# EJECTION_CIRCUIT.net
KiCad netlist of a schematic drawn in Altium Designer
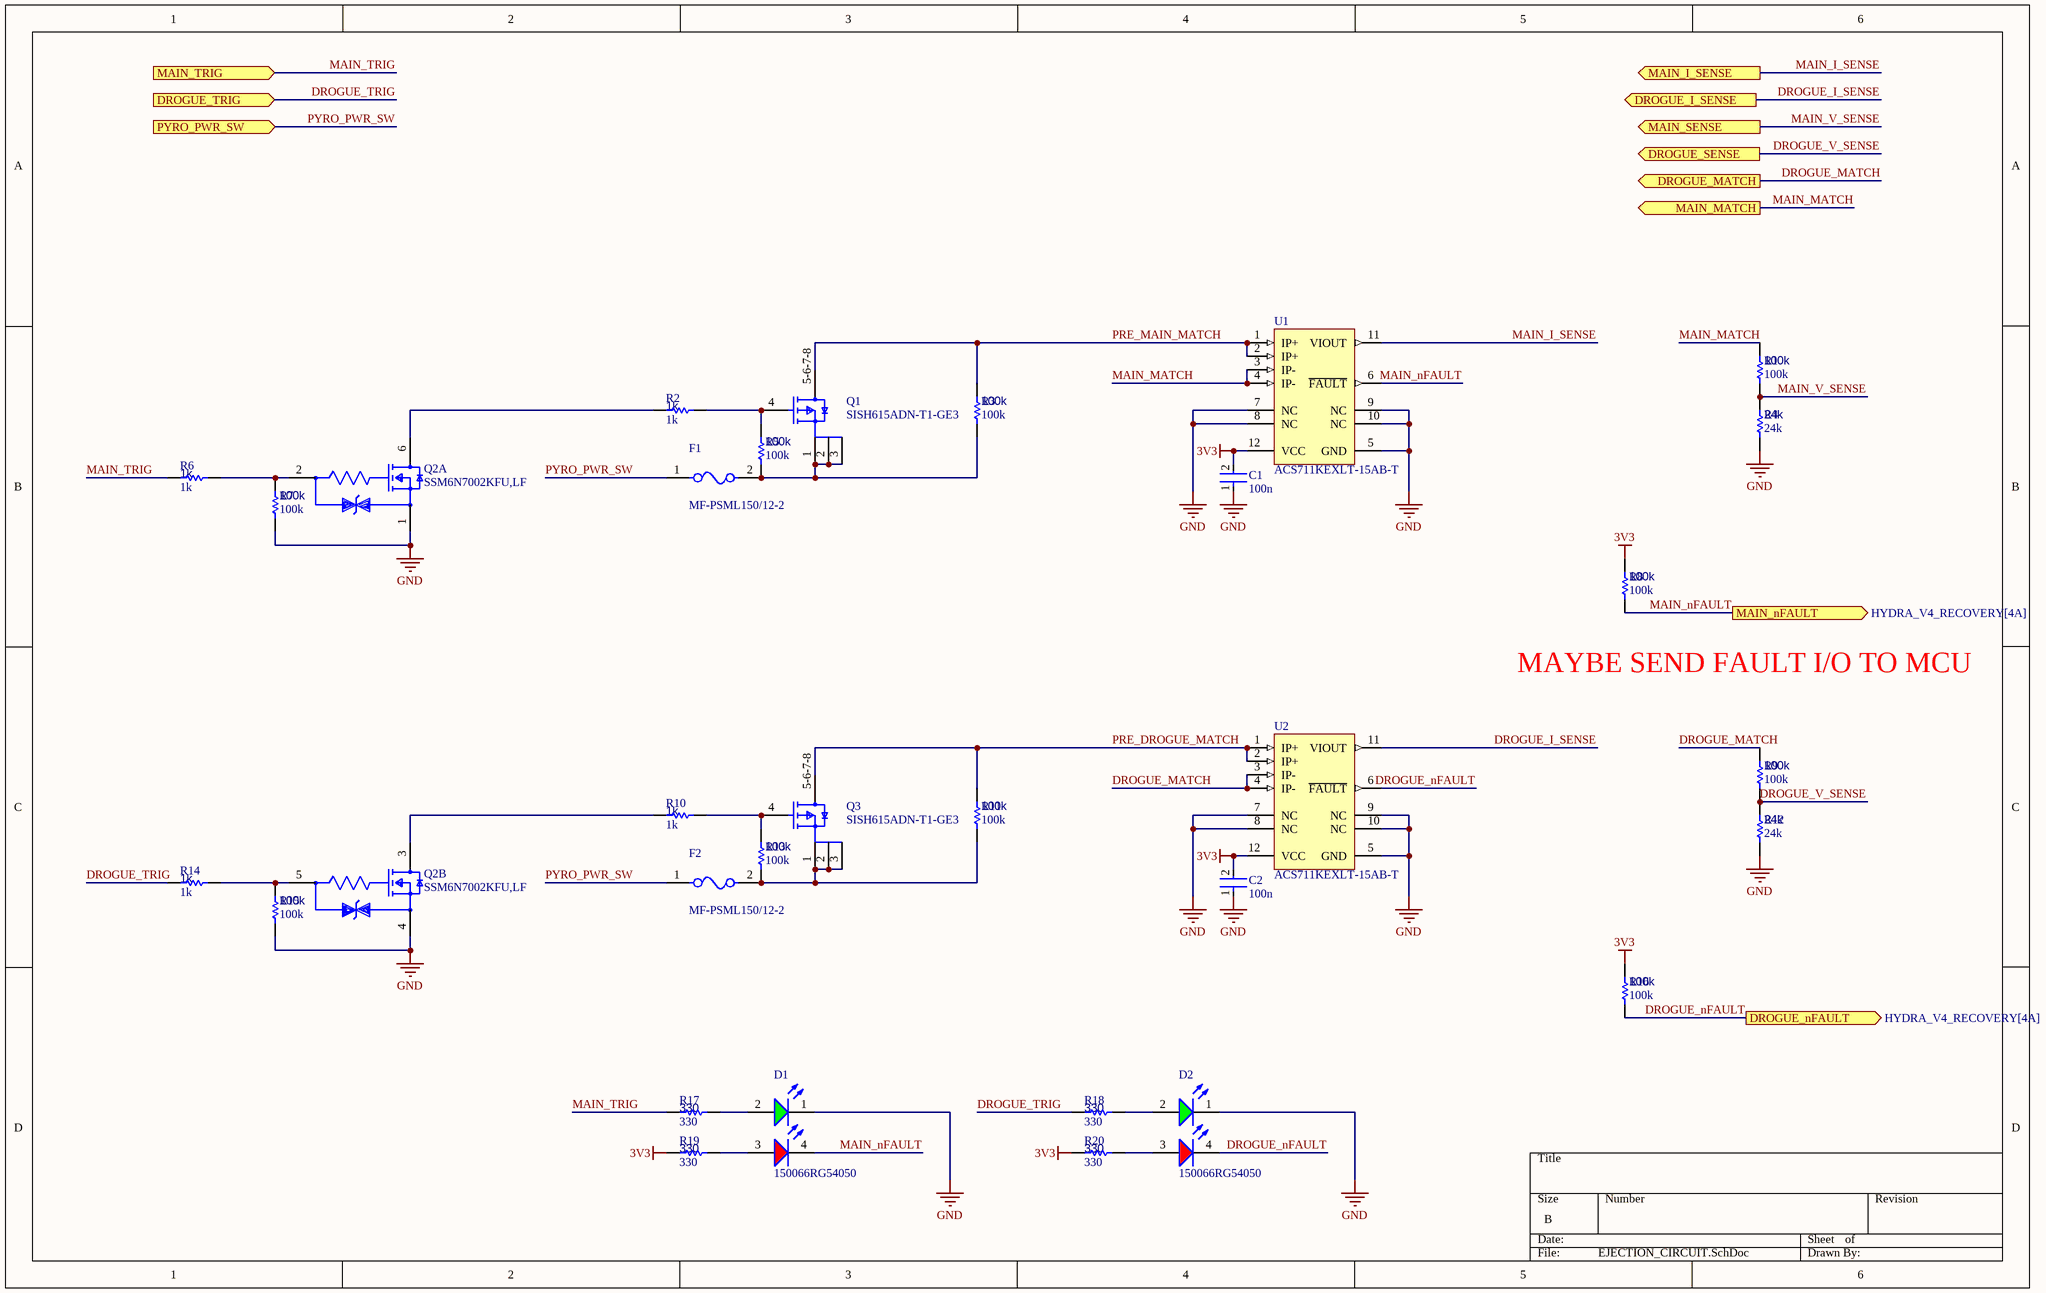
[diagram p0: EJECTION_CIRCUIT.SchDoc]

(export (version "E")
  (design (tool "Eeschema 10.0.6"))
  (components
    (comp (ref "C1")
      (value "100n")
      (footprint "FP-0402-L_1_0_0_05-W_0_5-IPC_A")
      (description "LARGE PADS, 0402 CAP, CHANGE COMMENT TO MATCH REAL P/N")
      (libsource (lib "Space Concordia") (part "b4654b650e69147ec39a6b967a45e02"))
    )
    (comp (ref "C2")
      (value "100n")
      (footprint "FP-0402-L_1_0_0_05-W_0_5-IPC_A")
      (description "LARGE PADS, 0402 CAP, CHANGE COMMENT TO MATCH REAL P/N")
      (libsource (lib "Space Concordia") (part "b4654b650e69147ec39a6b967a45e02"))
    )
    (comp (ref "D1")
      (value "150066RG54050")
      (footprint "WL-SBCD_0606")
      (description "Led, Red/Grn, 180Mcd/230Mcd, 624Nm/525Nm Rohs Compliant: Yes")
      (fields (field (name "SOURCE") "rgled.SchLib"))
      (libsource (lib "Space Concordia") (part "CMP-004-00034-2"))
    )
    (comp (ref "D2")
      (value "150066RG54050")
      (footprint "WL-SBCD_0606")
      (description "Led, Red/Grn, 180Mcd/230Mcd, 624Nm/525Nm Rohs Compliant: Yes")
      (fields (field (name "SOURCE") "rgled.SchLib"))
      (libsource (lib "Space Concordia") (part "CMP-004-00034-2"))
    )
    (comp (ref "F1")
      (value "MF-PSML150/12-2")
      (footprint "FP-MF-PSMF-MFG")
      (fields
        (field (name "OCTOPART") "https://octopart.com/mf-psmf010x-2-bourns-7483441")
        (field (name "MANUFACTURER PART NUMBER") "MF-PSMF010X-2")
        (field (name "MANUFACTURER") "Bourns Inc.")
      )
      (libsource (lib "Altium Content Vault") (part "5bcf9b9f640e542cf0359d10258e979"))
    )
    (comp (ref "F2")
      (value "MF-PSML150/12-2")
      (footprint "FP-MF-PSMF-MFG")
      (fields
        (field (name "OCTOPART") "https://octopart.com/mf-psmf010x-2-bourns-7483441")
        (field (name "MANUFACTURER PART NUMBER") "MF-PSMF010X-2")
        (field (name "MANUFACTURER") "Bourns Inc.")
      )
      (libsource (lib "Altium Content Vault") (part "5bcf9b9f640e542cf0359d10258e979"))
    )
    (comp (ref "Q1")
      (value "SISH615ADN-T1-GE3")
      (footprint "SISH615ADN-T1-GE3-Footprint-1")
      (description "Trans MOSFET P-CH 20V 22.1A 8-Pin PowerPAK 1212 EP T/R")
      (libsource (lib "Space Concordia") (part "CMP-013-00036-4"))
    )
    (comp (ref "Q2")
      (value "SSM6N7002KFU,LF")
      (footprint "FP-SSOP6-P-0_65A-MFG")
      (description "MOSFET 2N-CH 60V 0.3A")
      (libsource (lib "Altium Content Vault") (part "088aa6ac103fdeebe0d1c52ece6b7b9"))
    )
    (comp (ref "Q3")
      (value "SISH615ADN-T1-GE3")
      (footprint "SISH615ADN-T1-GE3-Footprint-1")
      (description "Trans MOSFET P-CH 20V 22.1A 8-Pin PowerPAK 1212 EP T/R")
      (libsource (lib "Space Concordia") (part "CMP-013-00036-4"))
    )
    (comp (ref "R1")
      (value "100k")
      (footprint "R0603B")
      (description "Resistor")
      (fields (field (name "ALTIUM_VALUE") "100k"))
      (libsource (lib "Space Concordia") (part "Resistor"))
    )
    (comp (ref "R2")
      (value "1k")
      (footprint "R0603B")
      (description "Resistor")
      (fields (field (name "ALTIUM_VALUE") "1k"))
      (libsource (lib "Space Concordia") (part "Resistor"))
    )
    (comp (ref "R3")
      (value "100k")
      (footprint "R0603B")
      (description "Resistor")
      (fields (field (name "ALTIUM_VALUE") "100k"))
      (libsource (lib "Space Concordia") (part "Resistor"))
    )
    (comp (ref "R4")
      (value "24k")
      (footprint "R0603B")
      (description "Resistor")
      (fields (field (name "ALTIUM_VALUE") "24k"))
      (libsource (lib "Space Concordia") (part "Resistor"))
    )
    (comp (ref "R5")
      (value "100k")
      (footprint "R0603B")
      (description "Resistor")
      (fields (field (name "ALTIUM_VALUE") "100k"))
      (libsource (lib "Space Concordia") (part "Resistor"))
    )
    (comp (ref "R6")
      (value "1k")
      (footprint "R0603B")
      (description "Resistor")
      (fields (field (name "ALTIUM_VALUE") "1k"))
      (libsource (lib "Space Concordia") (part "Resistor"))
    )
    (comp (ref "R7")
      (value "100k")
      (footprint "R0603B")
      (description "Resistor")
      (fields (field (name "ALTIUM_VALUE") "100k"))
      (libsource (lib "Space Concordia") (part "Resistor"))
    )
    (comp (ref "R8")
      (value "100k")
      (footprint "R0603B")
      (description "Resistor")
      (fields (field (name "ALTIUM_VALUE") "100k"))
      (libsource (lib "Space Concordia") (part "Resistor"))
    )
    (comp (ref "R9")
      (value "100k")
      (footprint "R0603B")
      (description "Resistor")
      (fields (field (name "ALTIUM_VALUE") "100k"))
      (libsource (lib "Space Concordia") (part "Resistor"))
    )
    (comp (ref "R10")
      (value "1k")
      (footprint "R0603B")
      (description "Resistor")
      (fields (field (name "ALTIUM_VALUE") "1k"))
      (libsource (lib "Space Concordia") (part "Resistor"))
    )
    (comp (ref "R11")
      (value "100k")
      (footprint "R0603B")
      (description "Resistor")
      (fields (field (name "ALTIUM_VALUE") "100k"))
      (libsource (lib "Space Concordia") (part "Resistor"))
    )
    (comp (ref "R12")
      (value "24k")
      (footprint "R0603B")
      (description "Resistor")
      (fields (field (name "ALTIUM_VALUE") "24k"))
      (libsource (lib "Space Concordia") (part "Resistor"))
    )
    (comp (ref "R13")
      (value "100k")
      (footprint "R0603B")
      (description "Resistor")
      (fields (field (name "ALTIUM_VALUE") "100k"))
      (libsource (lib "Space Concordia") (part "Resistor"))
    )
    (comp (ref "R14")
      (value "1k")
      (footprint "R0603B")
      (description "Resistor")
      (fields (field (name "ALTIUM_VALUE") "1k"))
      (libsource (lib "Space Concordia") (part "Resistor"))
    )
    (comp (ref "R15")
      (value "100k")
      (footprint "R0603B")
      (description "Resistor")
      (fields (field (name "ALTIUM_VALUE") "100k"))
      (libsource (lib "Space Concordia") (part "Resistor"))
    )
    (comp (ref "R16")
      (value "100k")
      (footprint "R0603B")
      (description "Resistor")
      (fields (field (name "ALTIUM_VALUE") "100k"))
      (libsource (lib "Space Concordia") (part "Resistor"))
    )
    (comp (ref "R17")
      (value "330")
      (footprint "R0603B")
      (description "Resistor")
      (fields (field (name "ALTIUM_VALUE") "330"))
      (libsource (lib "Space Concordia") (part "Resistor"))
    )
    (comp (ref "R18")
      (value "330")
      (footprint "R0603B")
      (description "Resistor")
      (fields (field (name "ALTIUM_VALUE") "330"))
      (libsource (lib "Space Concordia") (part "Resistor"))
    )
    (comp (ref "R19")
      (value "330")
      (footprint "R0603B")
      (description "Resistor")
      (fields (field (name "ALTIUM_VALUE") "330"))
      (libsource (lib "Space Concordia") (part "Resistor"))
    )
    (comp (ref "R20")
      (value "330")
      (footprint "R0603B")
      (description "Resistor")
      (fields (field (name "ALTIUM_VALUE") "330"))
      (libsource (lib "Space Concordia") (part "Resistor"))
    )
    (comp (ref "U1")
      (value "ACS711KEXLT-15AB-T")
      (footprint "ALEG-EX-12_V")
      (libsource (lib "Altium Content Vault") (part "ALEG-ACS711-QFN-12"))
    )
    (comp (ref "U2")
      (value "ACS711KEXLT-15AB-T")
      (footprint "ALEG-EX-12_V")
      (libsource (lib "Altium Content Vault") (part "ALEG-ACS711-QFN-12"))
    )
  )
  (nets
    (net (code "1") (name "/DROGUE_I_SENSE") (class "Default")
      (node (ref "U2") (pin "11") (pinfunction "VIOUT_11") (pintype "output"))
    )
    (net (code "2") (name "/DROGUE_MATCH") (class "Default")
      (node (ref "R9") (pin "2") (pinfunction "2_2") (pintype "passive"))
      (node (ref "U2") (pin "3") (pinfunction "IP-_3") (pintype "input"))
      (node (ref "U2") (pin "4") (pinfunction "IP-_4") (pintype "input"))
    )
    (net (code "3") (name "/DROGUE_TRIG") (class "Default")
      (node (ref "R14") (pin "2") (pinfunction "2_2") (pintype "passive"))
      (node (ref "R18") (pin "2") (pinfunction "2_2") (pintype "passive"))
    )
    (net (code "4") (name "/DROGUE_V_SENSE") (class "Default")
      (node (ref "R12") (pin "2") (pinfunction "2_2") (pintype "passive"))
      (node (ref "R9") (pin "1") (pinfunction "1_1") (pintype "passive"))
    )
    (net (code "5") (name "/DROGUE_nFAULT") (class "Default")
      (node (ref "D2") (pin "4") (pinfunction "K_4") (pintype "passive"))
      (node (ref "R16") (pin "1") (pinfunction "1_1") (pintype "passive"))
      (node (ref "U2") (pin "6") (pinfunction "~{FAULT}_6") (pintype "output"))
    )
    (net (code "6") (name "/MAIN_I_SENSE") (class "Default")
      (node (ref "U1") (pin "11") (pinfunction "VIOUT_11") (pintype "output"))
    )
    (net (code "7") (name "/MAIN_MATCH") (class "Default")
      (node (ref "R1") (pin "2") (pinfunction "2_2") (pintype "passive"))
      (node (ref "U1") (pin "3") (pinfunction "IP-_3") (pintype "input"))
      (node (ref "U1") (pin "4") (pinfunction "IP-_4") (pintype "input"))
    )
    (net (code "8") (name "/MAIN_TRIG") (class "Default")
      (node (ref "R17") (pin "2") (pinfunction "2_2") (pintype "passive"))
      (node (ref "R6") (pin "2") (pinfunction "2_2") (pintype "passive"))
    )
    (net (code "9") (name "/MAIN_V_SENSE") (class "Default")
      (node (ref "R1") (pin "1") (pinfunction "1_1") (pintype "passive"))
      (node (ref "R4") (pin "2") (pinfunction "2_2") (pintype "passive"))
    )
    (net (code "10") (name "/MAIN_nFAULT") (class "Default")
      (node (ref "D1") (pin "4") (pinfunction "K_4") (pintype "passive"))
      (node (ref "R8") (pin "1") (pinfunction "1_1") (pintype "passive"))
      (node (ref "U1") (pin "6") (pinfunction "~{FAULT}_6") (pintype "output"))
    )
    (net (code "11") (name "/PRE_DROGUE_MATCH") (class "Default")
      (node (ref "Q3") (pin "5-6-7-8") (pinfunction "D_5-6-7-8") (pintype "passive"))
      (node (ref "R11") (pin "2") (pinfunction "2_2") (pintype "passive"))
      (node (ref "U2") (pin "1") (pinfunction "IP+_1") (pintype "input"))
      (node (ref "U2") (pin "2") (pinfunction "IP+_2") (pintype "input"))
    )
    (net (code "12") (name "/PRE_MAIN_MATCH") (class "Default")
      (node (ref "Q1") (pin "5-6-7-8") (pinfunction "D_5-6-7-8") (pintype "passive"))
      (node (ref "R3") (pin "2") (pinfunction "2_2") (pintype "passive"))
      (node (ref "U1") (pin "1") (pinfunction "IP+_1") (pintype "input"))
      (node (ref "U1") (pin "2") (pinfunction "IP+_2") (pintype "input"))
    )
    (net (code "13") (name "/PYRO_PWR_SW") (class "Default")
      (node (ref "F1") (pin "1") (pinfunction "1_1") (pintype "passive"))
      (node (ref "F2") (pin "1") (pinfunction "1_1") (pintype "passive"))
    )
    (net (code "14") (name "3V3") (class "Default")
      (node (ref "C1") (pin "2") (pinfunction "2_2") (pintype "passive"))
      (node (ref "C2") (pin "2") (pinfunction "2_2") (pintype "passive"))
      (node (ref "R16") (pin "2") (pinfunction "2_2") (pintype "passive"))
      (node (ref "R19") (pin "2") (pinfunction "2_2") (pintype "passive"))
      (node (ref "R20") (pin "2") (pinfunction "2_2") (pintype "passive"))
      (node (ref "R8") (pin "2") (pinfunction "2_2") (pintype "passive"))
      (node (ref "U1") (pin "12") (pinfunction "VCC_12") (pintype "power_in"))
      (node (ref "U2") (pin "12") (pinfunction "VCC_12") (pintype "power_in"))
    )
    (net (code "15") (name "GND") (class "Default")
      (node (ref "C1") (pin "1") (pinfunction "1_1") (pintype "passive"))
      (node (ref "C2") (pin "1") (pinfunction "1_1") (pintype "passive"))
      (node (ref "D1") (pin "1") (pinfunction "K_1") (pintype "passive"))
      (node (ref "D2") (pin "1") (pinfunction "K_1") (pintype "passive"))
      (node (ref "Q2") (pin "1") (pinfunction "Source1_1") (pintype "passive"))
      (node (ref "Q2") (pin "4") (pinfunction "Source2_4") (pintype "passive"))
      (node (ref "R12") (pin "1") (pinfunction "1_1") (pintype "passive"))
      (node (ref "R15") (pin "1") (pinfunction "1_1") (pintype "passive"))
      (node (ref "R4") (pin "1") (pinfunction "1_1") (pintype "passive"))
      (node (ref "R7") (pin "1") (pinfunction "1_1") (pintype "passive"))
      (node (ref "U1") (pin "10") (pinfunction "NC_10") (pintype "passive"))
      (node (ref "U1") (pin "5") (pinfunction "GND_5") (pintype "power_in"))
      (node (ref "U1") (pin "7") (pinfunction "NC_7") (pintype "passive"))
      (node (ref "U1") (pin "8") (pinfunction "NC_8") (pintype "passive"))
      (node (ref "U1") (pin "9") (pinfunction "NC_9") (pintype "passive"))
      (node (ref "U2") (pin "10") (pinfunction "NC_10") (pintype "passive"))
      (node (ref "U2") (pin "5") (pinfunction "GND_5") (pintype "power_in"))
      (node (ref "U2") (pin "7") (pinfunction "NC_7") (pintype "passive"))
      (node (ref "U2") (pin "8") (pinfunction "NC_8") (pintype "passive"))
      (node (ref "U2") (pin "9") (pinfunction "NC_9") (pintype "passive"))
    )
    (net (code "16") (name "Net-(D1-A-Pad2)") (class "Default")
      (node (ref "D1") (pin "2") (pinfunction "A_2") (pintype "passive"))
      (node (ref "R17") (pin "1") (pinfunction "1_1") (pintype "passive"))
    )
    (net (code "17") (name "Net-(D1-A-Pad3)") (class "Default")
      (node (ref "D1") (pin "3") (pinfunction "A_3") (pintype "passive"))
      (node (ref "R19") (pin "1") (pinfunction "1_1") (pintype "passive"))
    )
    (net (code "18") (name "Net-(D2-A-Pad2)") (class "Default")
      (node (ref "D2") (pin "2") (pinfunction "A_2") (pintype "passive"))
      (node (ref "R18") (pin "1") (pinfunction "1_1") (pintype "passive"))
    )
    (net (code "19") (name "Net-(D2-A-Pad3)") (class "Default")
      (node (ref "D2") (pin "3") (pinfunction "A_3") (pintype "passive"))
      (node (ref "R20") (pin "1") (pinfunction "1_1") (pintype "passive"))
    )
    (net (code "20") (name "Net-(F1-Pad2)") (class "Default")
      (node (ref "F1") (pin "2") (pinfunction "2_2") (pintype "passive"))
      (node (ref "Q1") (pin "1") (pinfunction "S_1") (pintype "passive"))
      (node (ref "Q1") (pin "2") (pinfunction "S_2") (pintype "passive"))
      (node (ref "Q1") (pin "3") (pinfunction "S_3") (pintype "passive"))
      (node (ref "R3") (pin "1") (pinfunction "1_1") (pintype "passive"))
      (node (ref "R5") (pin "1") (pinfunction "1_1") (pintype "passive"))
    )
    (net (code "21") (name "Net-(F2-Pad2)") (class "Default")
      (node (ref "F2") (pin "2") (pinfunction "2_2") (pintype "passive"))
      (node (ref "Q3") (pin "1") (pinfunction "S_1") (pintype "passive"))
      (node (ref "Q3") (pin "2") (pinfunction "S_2") (pintype "passive"))
      (node (ref "Q3") (pin "3") (pinfunction "S_3") (pintype "passive"))
      (node (ref "R11") (pin "1") (pinfunction "1_1") (pintype "passive"))
      (node (ref "R13") (pin "1") (pinfunction "1_1") (pintype "passive"))
    )
    (net (code "22") (name "Net-(Q1-G)") (class "Default")
      (node (ref "Q1") (pin "4") (pinfunction "G_4") (pintype "passive"))
      (node (ref "R2") (pin "1") (pinfunction "1_1") (pintype "passive"))
      (node (ref "R5") (pin "2") (pinfunction "2_2") (pintype "passive"))
    )
    (net (code "23") (name "Net-(Q2A-Drain1)") (class "Default")
      (node (ref "Q2") (pin "6") (pinfunction "Drain1_6") (pintype "passive"))
      (node (ref "R2") (pin "2") (pinfunction "2_2") (pintype "passive"))
    )
    (net (code "24") (name "Net-(Q2A-Gate1)") (class "Default")
      (node (ref "Q2") (pin "2") (pinfunction "Gate1_2") (pintype "passive"))
      (node (ref "R6") (pin "1") (pinfunction "1_1") (pintype "passive"))
      (node (ref "R7") (pin "2") (pinfunction "2_2") (pintype "passive"))
    )
    (net (code "25") (name "Net-(Q2B-Drain2)") (class "Default")
      (node (ref "Q2") (pin "3") (pinfunction "Drain2_3") (pintype "passive"))
      (node (ref "R10") (pin "2") (pinfunction "2_2") (pintype "passive"))
    )
    (net (code "26") (name "Net-(Q2B-Gate2)") (class "Default")
      (node (ref "Q2") (pin "5") (pinfunction "Gate2_5") (pintype "passive"))
      (node (ref "R14") (pin "1") (pinfunction "1_1") (pintype "passive"))
      (node (ref "R15") (pin "2") (pinfunction "2_2") (pintype "passive"))
    )
    (net (code "27") (name "Net-(Q3-G)") (class "Default")
      (node (ref "Q3") (pin "4") (pinfunction "G_4") (pintype "passive"))
      (node (ref "R10") (pin "1") (pinfunction "1_1") (pintype "passive"))
      (node (ref "R13") (pin "2") (pinfunction "2_2") (pintype "passive"))
    )
  )
)
